# PhotonSMTTest1.net
KiCad netlist of a schematic drawn in EAGLE
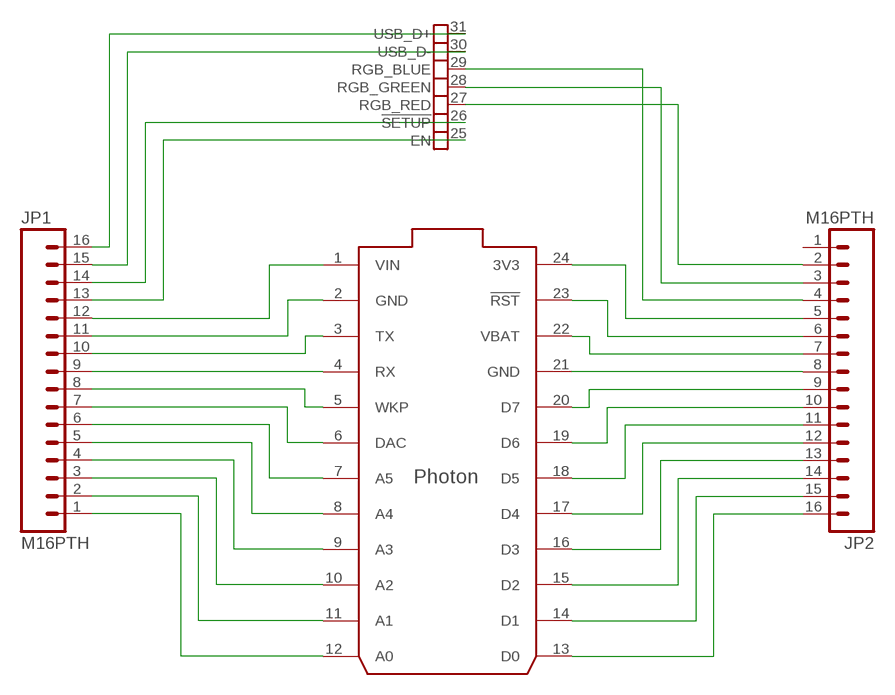
[diagram p0: schematic, sheet 1]

(export (version "E")
  (design (tool "Eeschema 10.0.6"))
  (components
    (comp (ref ".")
      (value "PHOTON_SMD")
      (footprint "eagle-import:PHOTON_SMD")
      (libsource (lib "eagle-import") (part "PHOTON_SMD"))
    )
    (comp (ref "JP1")
      (value "M16PTH")
      (footprint "eagle-import:1X16")
      (libsource (lib "eagle-import") (part "M16PTH"))
    )
    (comp (ref "JP2")
      (value "M16PTH")
      (footprint "eagle-import:1X16")
      (libsource (lib "eagle-import") (part "M16PTH"))
    )
  )
  (nets
    (net (code "1") (name "/GND") (class "Default")
      (node (ref ".") (pin "2") (pinfunction "GND_2") (pintype "power_in"))
      (node (ref ".") (pin "21") (pinfunction "GND_21") (pintype "power_in"))
      (node (ref "JP1") (pin "11") (pinfunction "11_11") (pintype "passive"))
      (node (ref "JP2") (pin "8") (pinfunction "8_8") (pintype "passive"))
    )
    (net (code "2") (name "Net-(.A-3V3)") (class "Default")
      (node (ref ".") (pin "24") (pinfunction "3V3_24") (pintype "power_in"))
      (node (ref "JP2") (pin "5") (pinfunction "5_5") (pintype "passive"))
    )
    (net (code "3") (name "Net-(.A-A0)") (class "Default")
      (node (ref ".") (pin "12") (pinfunction "A0_12") (pintype "bidirectional"))
      (node (ref "JP1") (pin "1") (pinfunction "1_1") (pintype "passive"))
    )
    (net (code "4") (name "Net-(.A-A1)") (class "Default")
      (node (ref ".") (pin "11") (pinfunction "A1_11") (pintype "bidirectional"))
      (node (ref "JP1") (pin "2") (pinfunction "2_2") (pintype "passive"))
    )
    (net (code "5") (name "Net-(.A-A2)") (class "Default")
      (node (ref ".") (pin "10") (pinfunction "A2_10") (pintype "bidirectional"))
      (node (ref "JP1") (pin "3") (pinfunction "3_3") (pintype "passive"))
    )
    (net (code "6") (name "Net-(.A-A3)") (class "Default")
      (node (ref ".") (pin "9") (pinfunction "A3_9") (pintype "bidirectional"))
      (node (ref "JP1") (pin "4") (pinfunction "4_4") (pintype "passive"))
    )
    (net (code "7") (name "Net-(.A-A4)") (class "Default")
      (node (ref ".") (pin "8") (pinfunction "A4_8") (pintype "bidirectional"))
      (node (ref "JP1") (pin "5") (pinfunction "5_5") (pintype "passive"))
    )
    (net (code "8") (name "Net-(.A-A5)") (class "Default")
      (node (ref ".") (pin "7") (pinfunction "A5_7") (pintype "bidirectional"))
      (node (ref "JP1") (pin "6") (pinfunction "6_6") (pintype "passive"))
    )
    (net (code "9") (name "Net-(.A-D0)") (class "Default")
      (node (ref ".") (pin "13") (pinfunction "D0_13") (pintype "bidirectional"))
      (node (ref "JP2") (pin "16") (pinfunction "16_16") (pintype "passive"))
    )
    (net (code "10") (name "Net-(.A-D1)") (class "Default")
      (node (ref ".") (pin "14") (pinfunction "D1_14") (pintype "bidirectional"))
      (node (ref "JP2") (pin "15") (pinfunction "15_15") (pintype "passive"))
    )
    (net (code "11") (name "Net-(.A-D2)") (class "Default")
      (node (ref ".") (pin "15") (pinfunction "D2_15") (pintype "bidirectional"))
      (node (ref "JP2") (pin "14") (pinfunction "14_14") (pintype "passive"))
    )
    (net (code "12") (name "Net-(.A-D3)") (class "Default")
      (node (ref ".") (pin "16") (pinfunction "D3_16") (pintype "bidirectional"))
      (node (ref "JP2") (pin "13") (pinfunction "13_13") (pintype "passive"))
    )
    (net (code "13") (name "Net-(.A-D4)") (class "Default")
      (node (ref ".") (pin "17") (pinfunction "D4_17") (pintype "bidirectional"))
      (node (ref "JP2") (pin "12") (pinfunction "12_12") (pintype "passive"))
    )
    (net (code "14") (name "Net-(.A-D5)") (class "Default")
      (node (ref ".") (pin "18") (pinfunction "D5_18") (pintype "bidirectional"))
      (node (ref "JP2") (pin "11") (pinfunction "11_11") (pintype "passive"))
    )
    (net (code "15") (name "Net-(.A-D6)") (class "Default")
      (node (ref ".") (pin "19") (pinfunction "D6_19") (pintype "bidirectional"))
      (node (ref "JP2") (pin "10") (pinfunction "10_10") (pintype "passive"))
    )
    (net (code "16") (name "Net-(.A-D7)") (class "Default")
      (node (ref ".") (pin "20") (pinfunction "D7_20") (pintype "bidirectional"))
      (node (ref "JP2") (pin "9") (pinfunction "9_9") (pintype "passive"))
    )
    (net (code "17") (name "Net-(.A-DAC)") (class "Default")
      (node (ref ".") (pin "6") (pinfunction "DAC_6") (pintype "bidirectional"))
      (node (ref "JP1") (pin "7") (pinfunction "7_7") (pintype "passive"))
    )
    (net (code "18") (name "Net-(.A-RX)") (class "Default")
      (node (ref ".") (pin "4") (pinfunction "RX_4") (pintype "bidirectional"))
      (node (ref "JP1") (pin "9") (pinfunction "9_9") (pintype "passive"))
    )
    (net (code "19") (name "Net-(.A-TX)") (class "Default")
      (node (ref ".") (pin "3") (pinfunction "TX_3") (pintype "bidirectional"))
      (node (ref "JP1") (pin "10") (pinfunction "10_10") (pintype "passive"))
    )
    (net (code "20") (name "Net-(.A-VBAT)") (class "Default")
      (node (ref ".") (pin "22") (pinfunction "VBAT_22") (pintype "power_in"))
      (node (ref "JP2") (pin "7") (pinfunction "7_7") (pintype "passive"))
    )
    (net (code "21") (name "Net-(.A-VIN)") (class "Default")
      (node (ref ".") (pin "1") (pinfunction "VIN_1") (pintype "power_in"))
      (node (ref "JP1") (pin "12") (pinfunction "12_12") (pintype "passive"))
    )
    (net (code "22") (name "Net-(.A-WKP)") (class "Default")
      (node (ref ".") (pin "5") (pinfunction "WKP_5") (pintype "bidirectional"))
      (node (ref "JP1") (pin "8") (pinfunction "8_8") (pintype "passive"))
    )
    (net (code "23") (name "Net-(.A-~{RST})") (class "Default")
      (node (ref ".") (pin "23") (pinfunction "~{RST}_23") (pintype "bidirectional"))
      (node (ref "JP2") (pin "6") (pinfunction "6_6") (pintype "passive"))
    )
    (net (code "24") (name "Net-(.B-EN)") (class "Default")
      (node (ref ".") (pin "25") (pinfunction "EN_25") (pintype "bidirectional"))
      (node (ref "JP1") (pin "13") (pinfunction "13_13") (pintype "passive"))
    )
    (net (code "25") (name "Net-(.B-RGB_BLUE)") (class "Default")
      (node (ref ".") (pin "29") (pinfunction "RGB_BLUE_29") (pintype "bidirectional"))
      (node (ref "JP2") (pin "4") (pinfunction "4_4") (pintype "passive"))
    )
    (net (code "26") (name "Net-(.B-RGB_GREEN)") (class "Default")
      (node (ref ".") (pin "28") (pinfunction "RGB_GREEN_28") (pintype "bidirectional"))
      (node (ref "JP2") (pin "3") (pinfunction "3_3") (pintype "passive"))
    )
    (net (code "27") (name "Net-(.B-RGB_RED)") (class "Default")
      (node (ref ".") (pin "27") (pinfunction "RGB_RED_27") (pintype "bidirectional"))
      (node (ref "JP2") (pin "2") (pinfunction "2_2") (pintype "passive"))
    )
    (net (code "28") (name "Net-(.B-USB_D+)") (class "Default")
      (node (ref ".") (pin "31") (pinfunction "USB_D+_31") (pintype "bidirectional"))
      (node (ref "JP1") (pin "16") (pinfunction "16_16") (pintype "passive"))
    )
    (net (code "29") (name "Net-(.B-USB_D-)") (class "Default")
      (node (ref ".") (pin "30") (pinfunction "USB_D-_30") (pintype "bidirectional"))
      (node (ref "JP1") (pin "15") (pinfunction "15_15") (pintype "passive"))
    )
    (net (code "30") (name "Net-(.B-~{SETUP})") (class "Default")
      (node (ref ".") (pin "26") (pinfunction "~{SETUP}_26") (pintype "bidirectional"))
      (node (ref "JP1") (pin "14") (pinfunction "14_14") (pintype "passive"))
    )
    (net (code "31") (name "unconnected-(JP2-Pad1)") (class "Default")
      (node (ref "JP2") (pin "1") (pinfunction "1_1") (pintype "passive"))
    )
  )
)
